# ModbusScanner.net
KiCad netlist of a schematic drawn in EAGLE
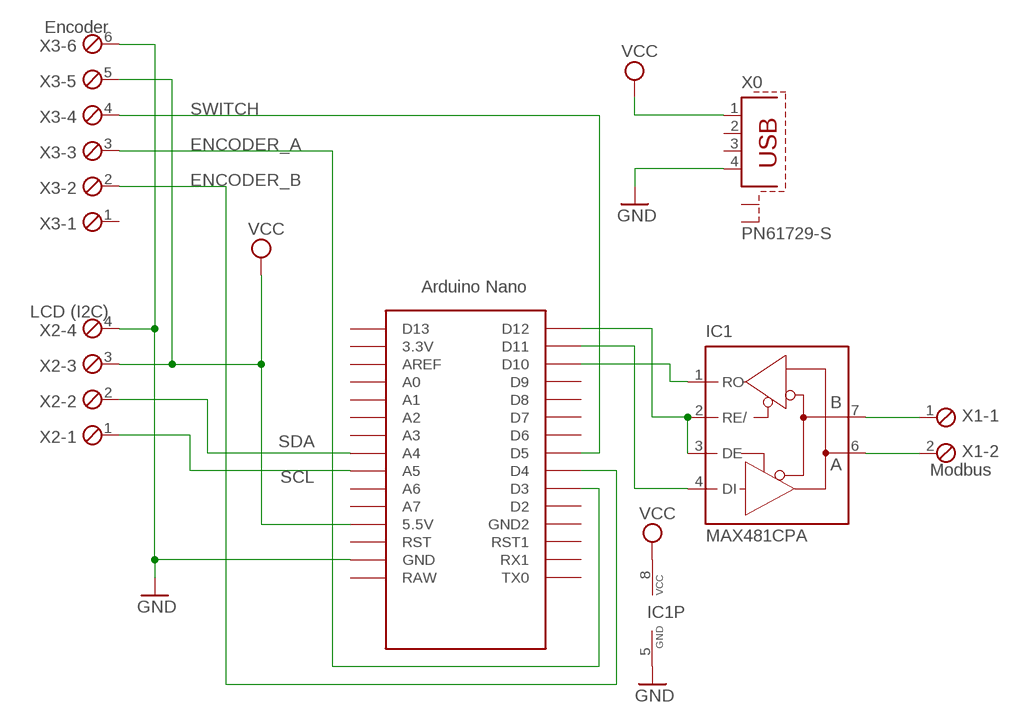
[diagram p0: schematic, sheet 1]

(export (version "E")
  (design (tool "Eeschema 10.0.6"))
  (components
    (comp (ref "IC1")
      (value "MAX481CPA")
      (footprint "eagle-import:DIL08")
      (fields (field (name "MPN") "MAX481CPA+"))
      (libsource (lib "eagle-import") (part "MAX481CPA"))
    )
    (comp (ref "U$1")
      (value "NANO")
      (footprint "eagle-import:NANO")
      (libsource (lib "eagle-import") (part "NANO"))
    )
    (comp (ref "X0")
      (value "PN61729-S")
      (footprint "eagle-import:PN61729-S")
      (libsource (lib "eagle-import") (part "PN61729-S"))
    )
    (comp (ref "X1")
      (value "Modbus")
      (footprint "eagle-import:2POL254")
      (libsource (lib "eagle-import") (part "MPT2"))
    )
    (comp (ref "X2")
      (value "LCD (I2C)")
      (footprint "eagle-import:4POL254")
      (libsource (lib "eagle-import") (part "MPT4"))
    )
    (comp (ref "X3")
      (value "Encoder")
      (footprint "eagle-import:6POL254")
      (libsource (lib "eagle-import") (part "MPT6"))
    )
  )
  (nets
    (net (code "1") (name "/ENCODER_A") (class "Default")
      (node (ref "U$1") (pin "D3") (pinfunction "D3_D3") (pintype "bidirectional"))
      (node (ref "X3") (pin "3") (pinfunction "1_3") (pintype "passive"))
    )
    (net (code "2") (name "/ENCODER_B") (class "Default")
      (node (ref "U$1") (pin "D4") (pinfunction "D4_D4") (pintype "bidirectional"))
      (node (ref "X3") (pin "2") (pinfunction "1_2") (pintype "passive"))
    )
    (net (code "3") (name "/SCL") (class "Default")
      (node (ref "U$1") (pin "A5") (pinfunction "A5_A5") (pintype "bidirectional"))
      (node (ref "X2") (pin "1") (pinfunction "1_1") (pintype "passive"))
    )
    (net (code "4") (name "/SDA") (class "Default")
      (node (ref "U$1") (pin "A4") (pinfunction "A4_A4") (pintype "bidirectional"))
      (node (ref "X2") (pin "2") (pinfunction "1_2") (pintype "passive"))
    )
    (net (code "5") (name "/SWITCH") (class "Default")
      (node (ref "U$1") (pin "D5") (pinfunction "D5_D5") (pintype "bidirectional"))
      (node (ref "X3") (pin "4") (pinfunction "1_4") (pintype "passive"))
    )
    (net (code "6") (name "GND") (class "Default")
      (node (ref "IC1") (pin "5") (pinfunction "GND_5") (pintype "power_in"))
      (node (ref "U$1") (pin "GND") (pinfunction "GND_GND") (pintype "bidirectional"))
      (node (ref "X0") (pin "4") (pinfunction "4_4") (pintype "passive"))
      (node (ref "X2") (pin "4") (pinfunction "1_4") (pintype "passive"))
      (node (ref "X3") (pin "6") (pinfunction "1_6") (pintype "passive"))
    )
    (net (code "7") (name "Net-(IC1A-A)") (class "Default")
      (node (ref "IC1") (pin "6") (pinfunction "A_6") (pintype "passive"))
      (node (ref "X1") (pin "2") (pinfunction "1_2") (pintype "passive"))
    )
    (net (code "8") (name "Net-(IC1A-B)") (class "Default")
      (node (ref "IC1") (pin "7") (pinfunction "B_7") (pintype "passive"))
      (node (ref "X1") (pin "1") (pinfunction "1_1") (pintype "passive"))
    )
    (net (code "9") (name "Net-(IC1A-DE)") (class "Default")
      (node (ref "IC1") (pin "2") (pinfunction "RE/_2") (pintype "input"))
      (node (ref "IC1") (pin "3") (pinfunction "DE_3") (pintype "input"))
      (node (ref "U$1") (pin "D12") (pinfunction "D12_D12") (pintype "bidirectional"))
    )
    (net (code "10") (name "Net-(IC1A-DI)") (class "Default")
      (node (ref "IC1") (pin "4") (pinfunction "DI_4") (pintype "input"))
      (node (ref "U$1") (pin "D11") (pinfunction "D11_D11") (pintype "bidirectional"))
    )
    (net (code "11") (name "Net-(IC1A-RO)") (class "Default")
      (node (ref "IC1") (pin "1") (pinfunction "RO_1") (pintype "output"))
      (node (ref "U$1") (pin "D10") (pinfunction "D10_D10") (pintype "bidirectional"))
    )
    (net (code "12") (name "VCC") (class "Default")
      (node (ref "IC1") (pin "8") (pinfunction "VCC_8") (pintype "power_in"))
      (node (ref "U$1") (pin "5V") (pinfunction "5.5V_5V") (pintype "bidirectional"))
      (node (ref "X0") (pin "1") (pinfunction "1_1") (pintype "passive"))
      (node (ref "X2") (pin "3") (pinfunction "1_3") (pintype "passive"))
      (node (ref "X3") (pin "5") (pinfunction "1_5") (pintype "passive"))
    )
    (net (code "13") (name "unconnected-(U$1-GND2-PadGND1)") (class "Default")
      (node (ref "U$1") (pin "GND1") (pinfunction "GND2_GND1") (pintype "bidirectional"))
    )
    (net (code "14") (name "unconnected-(U$1-Pad3.3V)") (class "Default")
      (node (ref "U$1") (pin "3.3V") (pinfunction "3.3V_3.3V") (pintype "bidirectional"))
    )
    (net (code "15") (name "unconnected-(U$1-PadA0)") (class "Default")
      (node (ref "U$1") (pin "A0") (pinfunction "A0_A0") (pintype "bidirectional"))
    )
    (net (code "16") (name "unconnected-(U$1-PadA1)") (class "Default")
      (node (ref "U$1") (pin "A1") (pinfunction "A1_A1") (pintype "bidirectional"))
    )
    (net (code "17") (name "unconnected-(U$1-PadA2)") (class "Default")
      (node (ref "U$1") (pin "A2") (pinfunction "A2_A2") (pintype "bidirectional"))
    )
    (net (code "18") (name "unconnected-(U$1-PadA3)") (class "Default")
      (node (ref "U$1") (pin "A3") (pinfunction "A3_A3") (pintype "bidirectional"))
    )
    (net (code "19") (name "unconnected-(U$1-PadA6)") (class "Default")
      (node (ref "U$1") (pin "A6") (pinfunction "A6_A6") (pintype "bidirectional"))
    )
    (net (code "20") (name "unconnected-(U$1-PadA7)") (class "Default")
      (node (ref "U$1") (pin "A7") (pinfunction "A7_A7") (pintype "bidirectional"))
    )
    (net (code "21") (name "unconnected-(U$1-PadAREF)") (class "Default")
      (node (ref "U$1") (pin "AREF") (pinfunction "AREF_AREF") (pintype "bidirectional"))
    )
    (net (code "22") (name "unconnected-(U$1-PadD2)") (class "Default")
      (node (ref "U$1") (pin "D2") (pinfunction "D2_D2") (pintype "bidirectional"))
    )
    (net (code "23") (name "unconnected-(U$1-PadD6)") (class "Default")
      (node (ref "U$1") (pin "D6") (pinfunction "D6_D6") (pintype "bidirectional"))
    )
    (net (code "24") (name "unconnected-(U$1-PadD7)") (class "Default")
      (node (ref "U$1") (pin "D7") (pinfunction "D7_D7") (pintype "bidirectional"))
    )
    (net (code "25") (name "unconnected-(U$1-PadD8)") (class "Default")
      (node (ref "U$1") (pin "D8") (pinfunction "D8_D8") (pintype "bidirectional"))
    )
    (net (code "26") (name "unconnected-(U$1-PadD9)") (class "Default")
      (node (ref "U$1") (pin "D9") (pinfunction "D9_D9") (pintype "bidirectional"))
    )
    (net (code "27") (name "unconnected-(U$1-PadD13)") (class "Default")
      (node (ref "U$1") (pin "D13") (pinfunction "D13_D13") (pintype "bidirectional"))
    )
    (net (code "28") (name "unconnected-(U$1-PadICSP1)") (class "Default")
      (node (ref "U$1") (pin "ICSP1") (pinfunction "ICSP1_ICSP1") (pintype "bidirectional"))
    )
    (net (code "29") (name "unconnected-(U$1-PadICSP2)") (class "Default")
      (node (ref "U$1") (pin "ICSP2") (pinfunction "ICSP2_ICSP2") (pintype "bidirectional"))
    )
    (net (code "30") (name "unconnected-(U$1-PadICSP3)") (class "Default")
      (node (ref "U$1") (pin "ICSP3") (pinfunction "ICSP3_ICSP3") (pintype "bidirectional"))
    )
    (net (code "31") (name "unconnected-(U$1-PadICSP4)") (class "Default")
      (node (ref "U$1") (pin "ICSP4") (pinfunction "ICSP4_ICSP4") (pintype "bidirectional"))
    )
    (net (code "32") (name "unconnected-(U$1-PadICSP5)") (class "Default")
      (node (ref "U$1") (pin "ICSP5") (pinfunction "ICSP5_ICSP5") (pintype "bidirectional"))
    )
    (net (code "33") (name "unconnected-(U$1-PadICSP6)") (class "Default")
      (node (ref "U$1") (pin "ICSP6") (pinfunction "ICSP6_ICSP6") (pintype "bidirectional"))
    )
    (net (code "34") (name "unconnected-(U$1-PadRAW)") (class "Default")
      (node (ref "U$1") (pin "RAW") (pinfunction "RAW_RAW") (pintype "bidirectional"))
    )
    (net (code "35") (name "unconnected-(U$1-PadRST)") (class "Default")
      (node (ref "U$1") (pin "RST") (pinfunction "RST_RST") (pintype "bidirectional"))
    )
    (net (code "36") (name "unconnected-(U$1-PadRST1)") (class "Default")
      (node (ref "U$1") (pin "RST1") (pinfunction "RST1_RST1") (pintype "bidirectional"))
    )
    (net (code "37") (name "unconnected-(U$1-PadRX1)") (class "Default")
      (node (ref "U$1") (pin "RX1") (pinfunction "RX1_RX1") (pintype "bidirectional"))
    )
    (net (code "38") (name "unconnected-(U$1-PadTX0)") (class "Default")
      (node (ref "U$1") (pin "TX0") (pinfunction "TX0_TX0") (pintype "bidirectional"))
    )
    (net (code "39") (name "unconnected-(X0-Pad2)") (class "Default")
      (node (ref "X0") (pin "2") (pinfunction "2_2") (pintype "passive"))
    )
    (net (code "40") (name "unconnected-(X0-Pad3)") (class "Default")
      (node (ref "X0") (pin "3") (pinfunction "3_3") (pintype "passive"))
    )
    (net (code "41") (name "unconnected-(X0-PadS1)") (class "Default")
      (node (ref "X0") (pin "S1") (pinfunction "S1_S1") (pintype "passive"))
    )
    (net (code "42") (name "unconnected-(X0-PadS2)") (class "Default")
      (node (ref "X0") (pin "S2") (pinfunction "S2_S2") (pintype "passive"))
    )
    (net (code "43") (name "unconnected-(X3-Pad1)") (class "Default")
      (node (ref "X3") (pin "1") (pinfunction "1_1") (pintype "passive"))
    )
  )
)
